# SCH_DHT11.net
KiCad netlist of a schematic drawn in Altium Designer
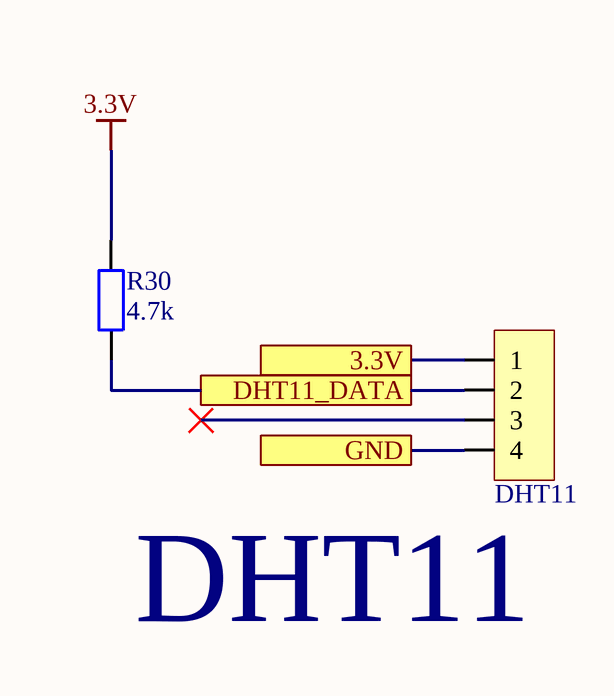
[diagram p0: SCH_DHT11.SchDoc]

(export (version "E")
  (design (tool "Eeschema 10.0.6"))
  (components
    (comp (ref "JP3")
      (value "DHT11")
      (footprint "JP 1x4 CT")
      (description "Cắm")
      (libsource (lib "Altium_Lib_by_KhueNguyenCreator") (part "JP 1x4 2.54 Cai Thang"))
    )
    (comp (ref "R30")
      (value "4.7k")
      (footprint "tro smd 0805")
      (description "Dán")
      (libsource (lib "Altium_Lib_by_KhueNguyenCreator") (part "Tro 0805 5% 4.7k"))
    )
  )
  (nets
    (net (code "1") (name "/DHT11_DATA") (class "Default")
      (node (ref "JP3") (pin "2") (pinfunction "2_2") (pintype "passive"))
      (node (ref "R30") (pin "1") (pinfunction "1_1") (pintype "passive"))
    )
    (net (code "2") (name "/GND") (class "Default")
      (node (ref "JP3") (pin "4") (pinfunction "4_4") (pintype "passive"))
    )
    (net (code "3") (name "3.3V") (class "Default")
      (node (ref "JP3") (pin "1") (pinfunction "1_1") (pintype "passive"))
      (node (ref "R30") (pin "2") (pinfunction "2_2") (pintype "passive"))
    )
    (net (code "4") (name "unconnected-(JP3-Pad3)") (class "Default")
      (node (ref "JP3") (pin "3") (pinfunction "3_3") (pintype "passive+no_connect"))
    )
  )
)
